# TM4C1.net
KiCad netlist of a schematic drawn in EAGLE
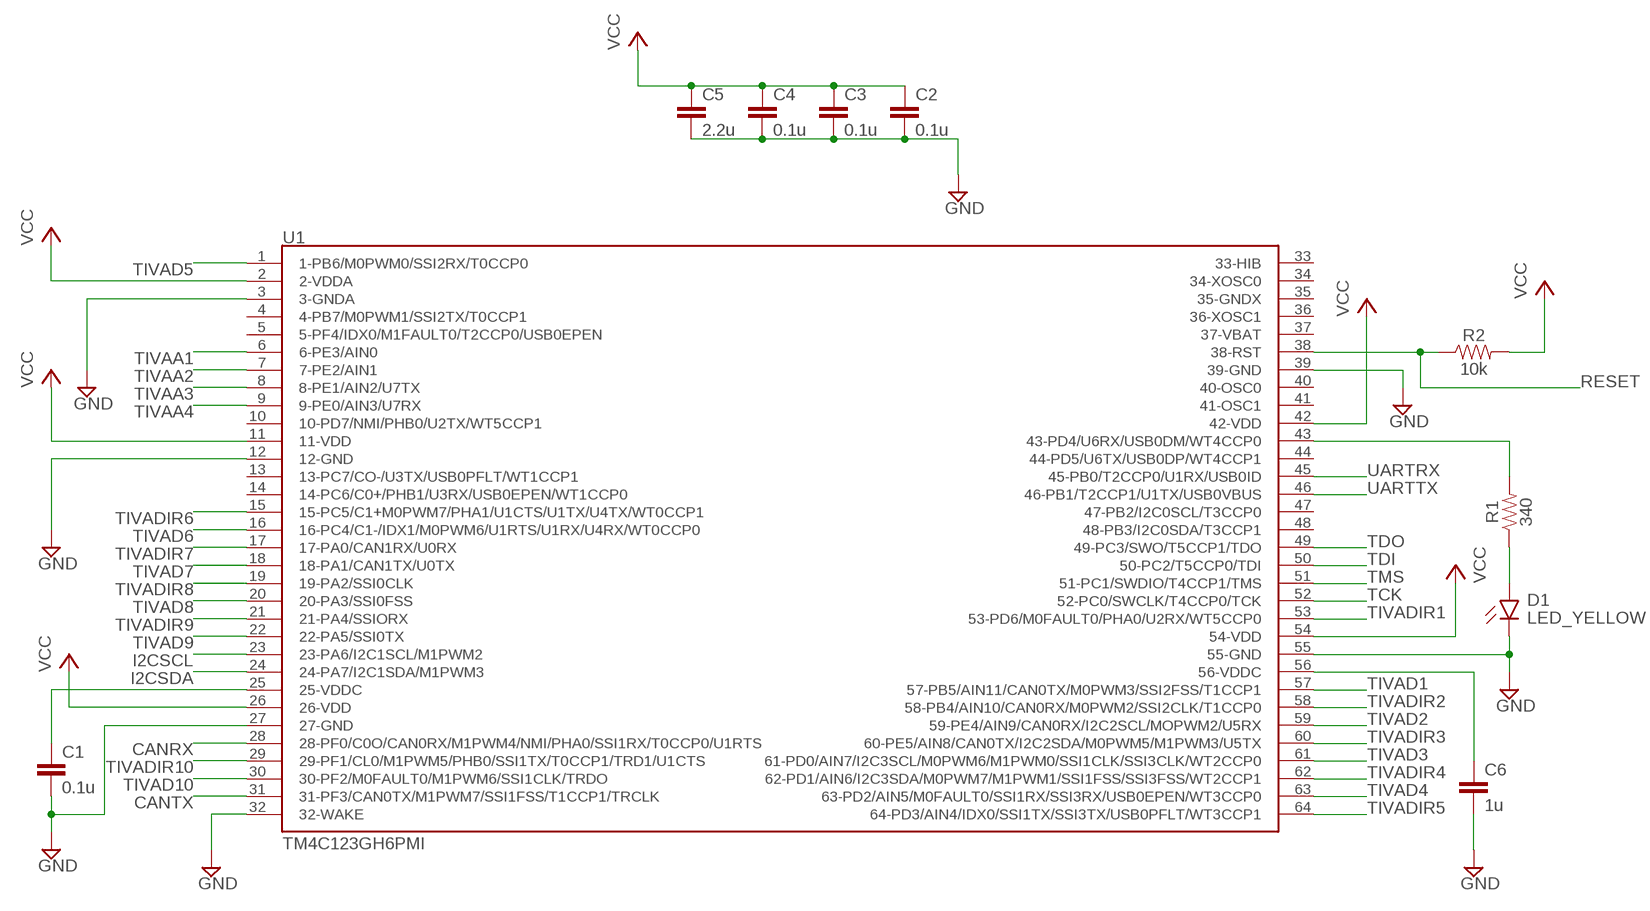
[diagram p0: schematic, sheet 1]

(export (version "E")
  (design (tool "Eeschema 10.0.6"))
  (components
    (comp (ref "C1")
      (value "0.1u")
      (footprint "eagle-import:C0603")
      (fields (field (name "MANUFACTURER") "Murata Electronics"))
      (libsource (lib "eagle-import") (part "CAP-0.1UF-0603-25V-X8R"))
    )
    (comp (ref "C2")
      (value "0.1u")
      (footprint "eagle-import:C0603")
      (fields (field (name "MANUFACTURER") "Murata Electronics"))
      (libsource (lib "eagle-import") (part "CAP-0.1UF-0603-25V-X8R"))
    )
    (comp (ref "C3")
      (value "0.1u")
      (footprint "eagle-import:C0603")
      (fields (field (name "MANUFACTURER") "Murata Electronics"))
      (libsource (lib "eagle-import") (part "CAP-0.1UF-0603-25V-X8R"))
    )
    (comp (ref "C4")
      (value "0.1u")
      (footprint "eagle-import:C0603")
      (fields (field (name "MANUFACTURER") "Murata Electronics"))
      (libsource (lib "eagle-import") (part "CAP-0.1UF-0603-25V-X8R"))
    )
    (comp (ref "C5")
      (value "2.2u")
      (footprint "eagle-import:C0603")
      (fields (field (name "MANUFACTURER") "Murata"))
      (libsource (lib "eagle-import") (part "CAP-2.2UF-0603-6.3V-X7R"))
    )
    (comp (ref "C6")
      (value "1u")
      (footprint "eagle-import:C0603")
      (fields (field (name "MANUFACTURER") "Murata"))
      (libsource (lib "eagle-import") (part "CAP-1UF-0603-25V-X7R"))
    )
    (comp (ref "D1")
      (value "LED_YELLOW")
      (footprint "eagle-import:LEDC1608X35N_FLAT-Y")
      (libsource (lib "eagle-import") (part "CHIP-FLAT-Y_0603-0.35MM"))
    )
    (comp (ref "R1")
      (value "340")
      (footprint "eagle-import:R0603")
      (fields (field (name "MANUFACTURER") "Panasonic"))
      (libsource (lib "eagle-import") (part "RES-340OHM-0603-1/10W-1%"))
    )
    (comp (ref "R2")
      (value "10k")
      (footprint "eagle-import:R0603")
      (fields (field (name "MANUFACTURER") "Panasonic"))
      (libsource (lib "eagle-import") (part "RES-10KOHM-0603-1/10W-1%"))
    )
    (comp (ref "U1")
      (value "TM4C123GH6PMI")
      (footprint "eagle-import:S-PQFP-G64")
      (fields (field (name "MFR") "Texas Instruments"))
      (libsource (lib "eagle-import") (part "TM4C123GH6PMI"))
    )
  )
  (nets
    (net (code "1") (name "/CANRX") (class "Default")
      (node (ref "U1") (pin "28") (pinfunction "28-PF0/C0O/CAN0RX/M1PWM4/NMI/PHA0/SSI1RX/T0CCP0/U1RTS_28") (pintype "bidirectional"))
    )
    (net (code "2") (name "/CANTX") (class "Default")
      (node (ref "U1") (pin "31") (pinfunction "31-PF3/CAN0TX/M1PWM7/SSI1FSS/T1CCP1/TRCLK_31") (pintype "bidirectional"))
    )
    (net (code "3") (name "/I2CSCL") (class "Default")
      (node (ref "U1") (pin "23") (pinfunction "23-PA6/I2C1SCL/M1PWM2_23") (pintype "bidirectional"))
    )
    (net (code "4") (name "/I2CSDA") (class "Default")
      (node (ref "U1") (pin "24") (pinfunction "24-PA7/I2C1SDA/M1PWM3_24") (pintype "bidirectional"))
    )
    (net (code "5") (name "/RESET") (class "Default")
      (node (ref "R2") (pin "1") (pinfunction "1_1") (pintype "passive"))
      (node (ref "U1") (pin "38") (pinfunction "38-RST_38") (pintype "bidirectional"))
    )
    (net (code "6") (name "/TCK") (class "Default")
      (node (ref "U1") (pin "52") (pinfunction "52-PC0/SWCLK/T4CCP0/TCK_52") (pintype "bidirectional"))
    )
    (net (code "7") (name "/TDI") (class "Default")
      (node (ref "U1") (pin "50") (pinfunction "50-PC2/T5CCP0/TDI_50") (pintype "bidirectional"))
    )
    (net (code "8") (name "/TDO") (class "Default")
      (node (ref "U1") (pin "49") (pinfunction "49-PC3/SWO/T5CCP1/TDO_49") (pintype "bidirectional"))
    )
    (net (code "9") (name "/TIVAA1") (class "Default")
      (node (ref "U1") (pin "6") (pinfunction "6-PE3/AIN0_6") (pintype "bidirectional"))
    )
    (net (code "10") (name "/TIVAA2") (class "Default")
      (node (ref "U1") (pin "7") (pinfunction "7-PE2/AIN1_7") (pintype "bidirectional"))
    )
    (net (code "11") (name "/TIVAA3") (class "Default")
      (node (ref "U1") (pin "8") (pinfunction "8-PE1/AIN2/U7TX_8") (pintype "bidirectional"))
    )
    (net (code "12") (name "/TIVAA4") (class "Default")
      (node (ref "U1") (pin "9") (pinfunction "9-PE0/AIN3/U7RX_9") (pintype "bidirectional"))
    )
    (net (code "13") (name "/TIVAD1") (class "Default")
      (node (ref "U1") (pin "57") (pinfunction "57-PB5/AIN11/CAN0TX/M0PWM3/SSI2FSS/T1CCP1_57") (pintype "bidirectional"))
    )
    (net (code "14") (name "/TIVAD2") (class "Default")
      (node (ref "U1") (pin "59") (pinfunction "59-PE4/AIN9/CAN0RX/I2C2SCL/MOPWM2/U5RX_59") (pintype "bidirectional"))
    )
    (net (code "15") (name "/TIVAD3") (class "Default")
      (node (ref "U1") (pin "61") (pinfunction "61-PD0/AIN7/I2C3SCL/M0PWM6/M1PWM0/SSI1CLK/SSI3CLK/WT2CCP0_61") (pintype "bidirectional"))
    )
    (net (code "16") (name "/TIVAD4") (class "Default")
      (node (ref "U1") (pin "63") (pinfunction "63-PD2/AIN5/M0FAULT0/SSI1RX/SSI3RX/USB0EPEN/WT3CCP0_63") (pintype "bidirectional"))
    )
    (net (code "17") (name "/TIVAD5") (class "Default")
      (node (ref "U1") (pin "1") (pinfunction "1-PB6/M0PWM0/SSI2RX/T0CCP0_1") (pintype "bidirectional"))
    )
    (net (code "18") (name "/TIVAD6") (class "Default")
      (node (ref "U1") (pin "16") (pinfunction "16-PC4/C1-/IDX1/M0PWM6/U1RTS/U1RX/U4RX/WT0CCP0_16") (pintype "bidirectional"))
    )
    (net (code "19") (name "/TIVAD7") (class "Default")
      (node (ref "U1") (pin "18") (pinfunction "18-PA1/CAN1TX/U0TX_18") (pintype "bidirectional"))
    )
    (net (code "20") (name "/TIVAD8") (class "Default")
      (node (ref "U1") (pin "20") (pinfunction "20-PA3/SSI0FSS_20") (pintype "bidirectional"))
    )
    (net (code "21") (name "/TIVAD9") (class "Default")
      (node (ref "U1") (pin "22") (pinfunction "22-PA5/SSI0TX_22") (pintype "bidirectional"))
    )
    (net (code "22") (name "/TIVAD10") (class "Default")
      (node (ref "U1") (pin "30") (pinfunction "30-PF2/M0FAULT0/M1PWM6/SSI1CLK/TRDO_30") (pintype "bidirectional"))
    )
    (net (code "23") (name "/TIVADIR1") (class "Default")
      (node (ref "U1") (pin "53") (pinfunction "53-PD6/M0FAULT0/PHA0/U2RX/WT5CCP0_53") (pintype "bidirectional"))
    )
    (net (code "24") (name "/TIVADIR2") (class "Default")
      (node (ref "U1") (pin "58") (pinfunction "58-PB4/AIN10/CAN0RX/M0PWM2/SSI2CLK/T1CCP0_58") (pintype "bidirectional"))
    )
    (net (code "25") (name "/TIVADIR3") (class "Default")
      (node (ref "U1") (pin "60") (pinfunction "60-PE5/AIN8/CAN0TX/I2C2SDA/M0PWM5/M1PWM3/U5TX_60") (pintype "bidirectional"))
    )
    (net (code "26") (name "/TIVADIR4") (class "Default")
      (node (ref "U1") (pin "62") (pinfunction "62-PD1/AIN6/I2C3SDA/M0PWM7/M1PWM1/SSI1FSS/SSI3FSS/WT2CCP1_62") (pintype "bidirectional"))
    )
    (net (code "27") (name "/TIVADIR5") (class "Default")
      (node (ref "U1") (pin "64") (pinfunction "64-PD3/AIN4/IDX0/SSI1TX/SSI3TX/USB0PFLT/WT3CCP1_64") (pintype "bidirectional"))
    )
    (net (code "28") (name "/TIVADIR6") (class "Default")
      (node (ref "U1") (pin "15") (pinfunction "15-PC5/C1+M0PWM7/PHA1/U1CTS/U1TX/U4TX/WT0CCP1_15") (pintype "bidirectional"))
    )
    (net (code "29") (name "/TIVADIR7") (class "Default")
      (node (ref "U1") (pin "17") (pinfunction "17-PA0/CAN1RX/U0RX_17") (pintype "bidirectional"))
    )
    (net (code "30") (name "/TIVADIR8") (class "Default")
      (node (ref "U1") (pin "19") (pinfunction "19-PA2/SSI0CLK_19") (pintype "bidirectional"))
    )
    (net (code "31") (name "/TIVADIR9") (class "Default")
      (node (ref "U1") (pin "21") (pinfunction "21-PA4/SSIORX_21") (pintype "bidirectional"))
    )
    (net (code "32") (name "/TIVADIR10") (class "Default")
      (node (ref "U1") (pin "29") (pinfunction "29-PF1/CL0/M1PWM5/PHB0/SSI1TX/T0CCP1/TRD1/U1CTS_29") (pintype "bidirectional"))
    )
    (net (code "33") (name "/TMS") (class "Default")
      (node (ref "U1") (pin "51") (pinfunction "51-PC1/SWDIO/T4CCP1/TMS_51") (pintype "bidirectional"))
    )
    (net (code "34") (name "/UARTRX") (class "Default")
      (node (ref "U1") (pin "45") (pinfunction "45-PB0/T2CCP0/U1RX/USB0ID_45") (pintype "bidirectional"))
    )
    (net (code "35") (name "/UARTTX") (class "Default")
      (node (ref "U1") (pin "46") (pinfunction "46-PB1/T2CCP1/U1TX/USB0VBUS_46") (pintype "bidirectional"))
    )
    (net (code "36") (name "GND") (class "Default")
      (node (ref "C1") (pin "2") (pinfunction "2_2") (pintype "passive"))
      (node (ref "C2") (pin "2") (pinfunction "2_2") (pintype "passive"))
      (node (ref "C3") (pin "2") (pinfunction "2_2") (pintype "passive"))
      (node (ref "C4") (pin "2") (pinfunction "2_2") (pintype "passive"))
      (node (ref "C5") (pin "2") (pinfunction "2_2") (pintype "passive"))
      (node (ref "C6") (pin "2") (pinfunction "2_2") (pintype "passive"))
      (node (ref "D1") (pin "C") (pinfunction "C_C") (pintype "passive"))
      (node (ref "U1") (pin "12") (pinfunction "12-GND_12") (pintype "bidirectional"))
      (node (ref "U1") (pin "27") (pinfunction "27-GND_27") (pintype "bidirectional"))
      (node (ref "U1") (pin "3") (pinfunction "3-GNDA_3") (pintype "bidirectional"))
      (node (ref "U1") (pin "32") (pinfunction "32-WAKE_32") (pintype "bidirectional"))
      (node (ref "U1") (pin "39") (pinfunction "39-GND_39") (pintype "bidirectional"))
      (node (ref "U1") (pin "55") (pinfunction "55-GND_55") (pintype "bidirectional"))
    )
    (net (code "37") (name "Net-(D1-PadA)") (class "Default")
      (node (ref "D1") (pin "A") (pinfunction "A_A") (pintype "passive"))
      (node (ref "R1") (pin "1") (pinfunction "1_1") (pintype "passive"))
    )
    (net (code "38") (name "Net-(U1-25-VDDC)") (class "Default")
      (node (ref "C1") (pin "1") (pinfunction "1_1") (pintype "passive"))
      (node (ref "U1") (pin "25") (pinfunction "25-VDDC_25") (pintype "bidirectional"))
    )
    (net (code "39") (name "Net-(U1-43-PD4{slash}U6RX{slash}USB0DM{slash}WT4CCP0)") (class "Default")
      (node (ref "R1") (pin "2") (pinfunction "2_2") (pintype "passive"))
      (node (ref "U1") (pin "43") (pinfunction "43-PD4/U6RX/USB0DM/WT4CCP0_43") (pintype "bidirectional"))
    )
    (net (code "40") (name "Net-(U1-56-VDDC)") (class "Default")
      (node (ref "C6") (pin "1") (pinfunction "1_1") (pintype "passive"))
      (node (ref "U1") (pin "56") (pinfunction "56-VDDC_56") (pintype "bidirectional"))
    )
    (net (code "41") (name "VCC") (class "Default")
      (node (ref "C2") (pin "1") (pinfunction "1_1") (pintype "passive"))
      (node (ref "C3") (pin "1") (pinfunction "1_1") (pintype "passive"))
      (node (ref "C4") (pin "1") (pinfunction "1_1") (pintype "passive"))
      (node (ref "C5") (pin "1") (pinfunction "1_1") (pintype "passive"))
      (node (ref "R2") (pin "2") (pinfunction "2_2") (pintype "passive"))
      (node (ref "U1") (pin "11") (pinfunction "11-VDD_11") (pintype "bidirectional"))
      (node (ref "U1") (pin "2") (pinfunction "2-VDDA_2") (pintype "bidirectional"))
      (node (ref "U1") (pin "26") (pinfunction "26-VDD_26") (pintype "bidirectional"))
      (node (ref "U1") (pin "42") (pinfunction "42-VDD_42") (pintype "bidirectional"))
      (node (ref "U1") (pin "54") (pinfunction "54-VDD_54") (pintype "bidirectional"))
    )
    (net (code "42") (name "unconnected-(U1-4-PB7{slash}M0PWM1{slash}SSI2TX{slash}T0CCP1-Pad4)") (class "Default")
      (node (ref "U1") (pin "4") (pinfunction "4-PB7/M0PWM1/SSI2TX/T0CCP1_4") (pintype "bidirectional"))
    )
    (net (code "43") (name "unconnected-(U1-5-PF4{slash}IDX0{slash}M1FAULT0{slash}T2CCP0{slash}USB0EPEN-Pad5)") (class "Default")
      (node (ref "U1") (pin "5") (pinfunction "5-PF4/IDX0/M1FAULT0/T2CCP0/USB0EPEN_5") (pintype "bidirectional"))
    )
    (net (code "44") (name "unconnected-(U1-10-PD7{slash}NMI{slash}PHB0{slash}U2TX{slash}WT5CCP1-Pad10)") (class "Default")
      (node (ref "U1") (pin "10") (pinfunction "10-PD7/NMI/PHB0/U2TX/WT5CCP1_10") (pintype "bidirectional"))
    )
    (net (code "45") (name "unconnected-(U1-13-PC7{slash}CO-{slash}U3TX{slash}USB0PFLT{slash}WT1CCP1-Pad13)") (class "Default")
      (node (ref "U1") (pin "13") (pinfunction "13-PC7/CO-/U3TX/USB0PFLT/WT1CCP1_13") (pintype "bidirectional"))
    )
    (net (code "46") (name "unconnected-(U1-14-PC6{slash}C0+{slash}PHB1{slash}U3RX{slash}USB0EPEN{slash}WT1CCP0-Pad14)") (class "Default")
      (node (ref "U1") (pin "14") (pinfunction "14-PC6/C0+/PHB1/U3RX/USB0EPEN/WT1CCP0_14") (pintype "bidirectional"))
    )
    (net (code "47") (name "unconnected-(U1-33-HIB-Pad33)") (class "Default")
      (node (ref "U1") (pin "33") (pinfunction "33-HIB_33") (pintype "bidirectional"))
    )
    (net (code "48") (name "unconnected-(U1-34-XOSC0-Pad34)") (class "Default")
      (node (ref "U1") (pin "34") (pinfunction "34-XOSC0_34") (pintype "bidirectional"))
    )
    (net (code "49") (name "unconnected-(U1-35-GNDX-Pad35)") (class "Default")
      (node (ref "U1") (pin "35") (pinfunction "35-GNDX_35") (pintype "bidirectional"))
    )
    (net (code "50") (name "unconnected-(U1-36-XOSC1-Pad36)") (class "Default")
      (node (ref "U1") (pin "36") (pinfunction "36-XOSC1_36") (pintype "bidirectional"))
    )
    (net (code "51") (name "unconnected-(U1-37-VBAT-Pad37)") (class "Default")
      (node (ref "U1") (pin "37") (pinfunction "37-VBAT_37") (pintype "bidirectional"))
    )
    (net (code "52") (name "unconnected-(U1-40-OSC0-Pad40)") (class "Default")
      (node (ref "U1") (pin "40") (pinfunction "40-OSC0_40") (pintype "bidirectional"))
    )
    (net (code "53") (name "unconnected-(U1-41-OSC1-Pad41)") (class "Default")
      (node (ref "U1") (pin "41") (pinfunction "41-OSC1_41") (pintype "bidirectional"))
    )
    (net (code "54") (name "unconnected-(U1-44-PD5{slash}U6TX{slash}USB0DP{slash}WT4CCP1-Pad44)") (class "Default")
      (node (ref "U1") (pin "44") (pinfunction "44-PD5/U6TX/USB0DP/WT4CCP1_44") (pintype "bidirectional"))
    )
    (net (code "55") (name "unconnected-(U1-47-PB2{slash}I2C0SCL{slash}T3CCP0-Pad47)") (class "Default")
      (node (ref "U1") (pin "47") (pinfunction "47-PB2/I2C0SCL/T3CCP0_47") (pintype "bidirectional"))
    )
    (net (code "56") (name "unconnected-(U1-48-PB3{slash}I2C0SDA{slash}T3CCP1-Pad48)") (class "Default")
      (node (ref "U1") (pin "48") (pinfunction "48-PB3/I2C0SDA/T3CCP1_48") (pintype "bidirectional"))
    )
  )
)
